# STM_IC.net
KiCad netlist of a schematic drawn in Altium Designer
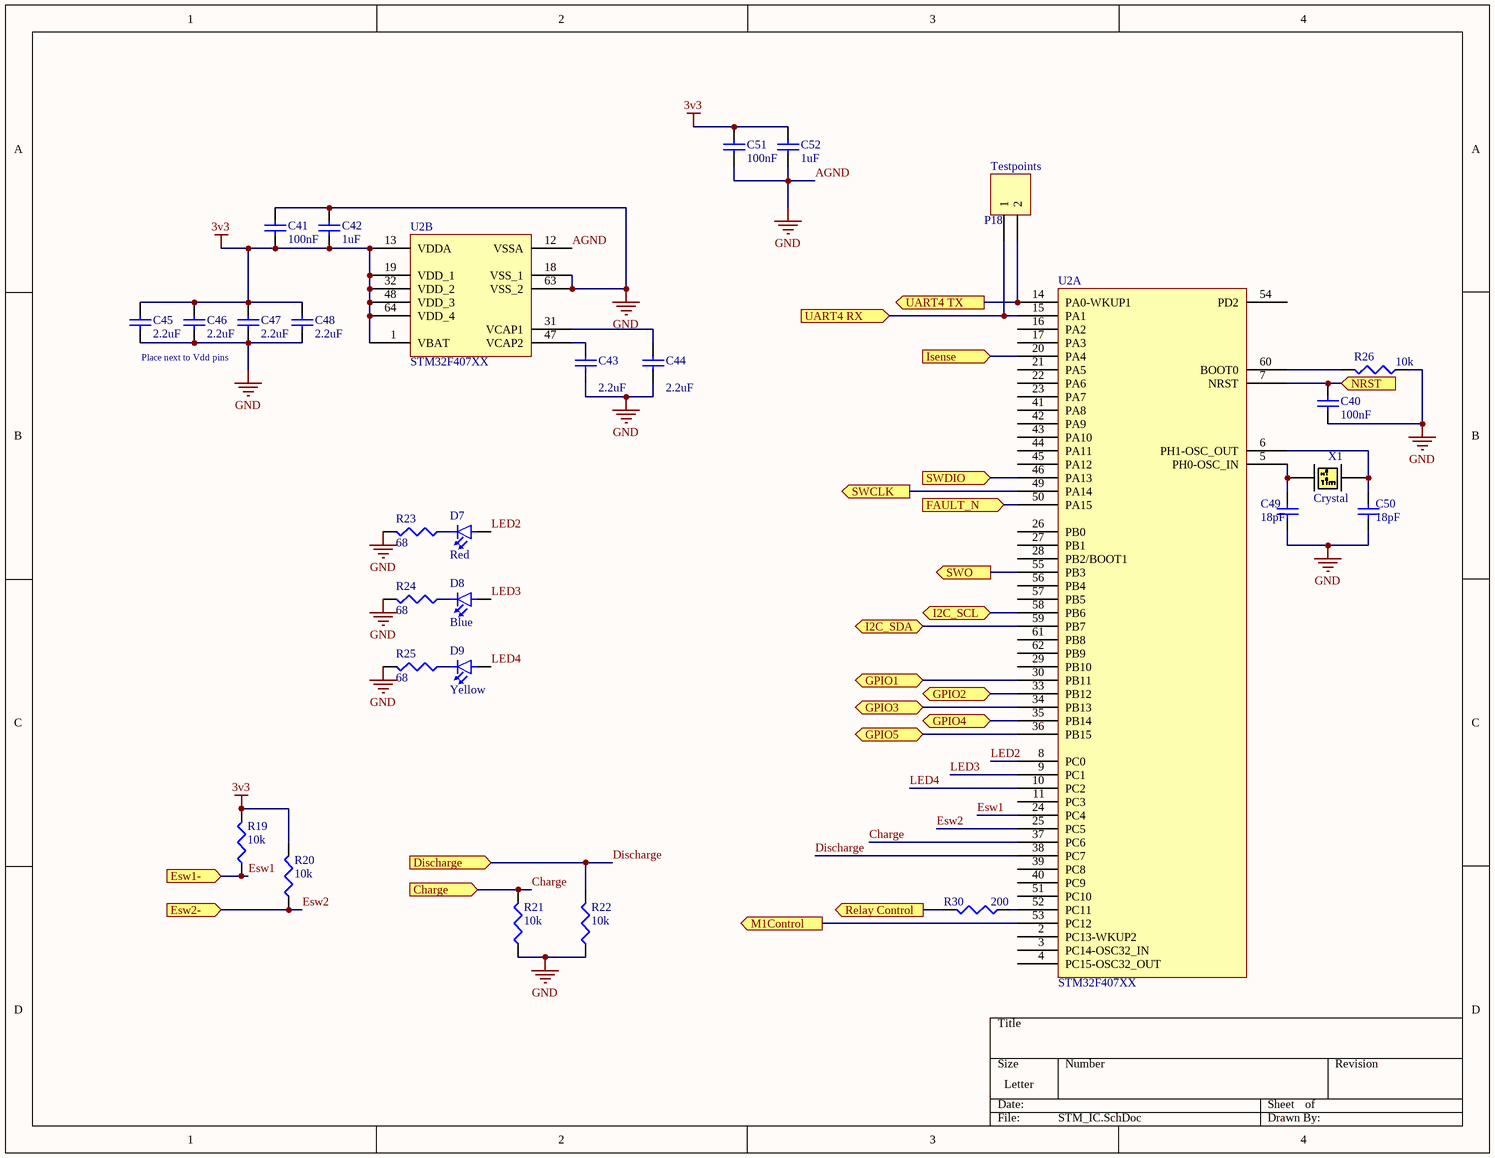
[diagram p0: STM_IC.SchDoc]

(export (version "E")
  (design (tool "Eeschema 10.0.6"))
  (components
    (comp (ref "C40")
      (value "100nF")
      (footprint "SMD0603")
      (description "Ceramic Chip Capacitor")
      (fields (field (name "Comment") "Cap"))
      (libsource (lib "Components") (part "Capacitor Ceramic"))
    )
    (comp (ref "C41")
      (value "100nF")
      (footprint "SMD0603")
      (description "Ceramic Chip Capacitor")
      (fields (field (name "Comment") "Cap"))
      (libsource (lib "Components") (part "Capacitor Ceramic"))
    )
    (comp (ref "C42")
      (value "1uF")
      (footprint "SMD0603")
      (description "Ceramic Chip Capacitor")
      (fields (field (name "Comment") "Cap"))
      (libsource (lib "Components") (part "Capacitor Ceramic"))
    )
    (comp (ref "C43")
      (value "2.2uF")
      (footprint "SMD0603")
      (description "Ceramic Chip Capacitor")
      (fields (field (name "Comment") "Cap"))
      (libsource (lib "Components") (part "Capacitor Ceramic"))
    )
    (comp (ref "C44")
      (value "2.2uF")
      (footprint "SMD0603")
      (description "Ceramic Chip Capacitor")
      (fields (field (name "Comment") "Cap"))
      (libsource (lib "Components") (part "Capacitor Ceramic"))
    )
    (comp (ref "C45")
      (value "2.2uF")
      (footprint "SMD0603")
      (description "Ceramic Chip Capacitor")
      (fields (field (name "Comment") "Cap"))
      (libsource (lib "Components") (part "Capacitor Ceramic"))
    )
    (comp (ref "C46")
      (value "2.2uF")
      (footprint "SMD0603")
      (description "Ceramic Chip Capacitor")
      (fields (field (name "Comment") "Cap"))
      (libsource (lib "Components") (part "Capacitor Ceramic"))
    )
    (comp (ref "C47")
      (value "2.2uF")
      (footprint "SMD0603")
      (description "Ceramic Chip Capacitor")
      (fields (field (name "Comment") "Cap"))
      (libsource (lib "Components") (part "Capacitor Ceramic"))
    )
    (comp (ref "C48")
      (value "2.2uF")
      (footprint "SMD0603")
      (description "Ceramic Chip Capacitor")
      (fields (field (name "Comment") "Cap"))
      (libsource (lib "Components") (part "Capacitor Ceramic"))
    )
    (comp (ref "C49")
      (value "18pF")
      (footprint "SMD0603")
      (description "Ceramic Chip Capacitor")
      (fields (field (name "Comment") "Cap"))
      (libsource (lib "Components") (part "Capacitor Ceramic"))
    )
    (comp (ref "C50")
      (value "18pF")
      (footprint "SMD0603")
      (description "Ceramic Chip Capacitor")
      (fields (field (name "Comment") "Cap"))
      (libsource (lib "Components") (part "Capacitor Ceramic"))
    )
    (comp (ref "C51")
      (value "100nF")
      (footprint "SMD0603")
      (description "Ceramic Chip Capacitor")
      (fields (field (name "Comment") "Cap"))
      (libsource (lib "Components") (part "Capacitor Ceramic"))
    )
    (comp (ref "C52")
      (value "1uF")
      (footprint "SMD0603")
      (description "Ceramic Chip Capacitor")
      (fields (field (name "Comment") "Cap"))
      (libsource (lib "Components") (part "Capacitor Ceramic"))
    )
    (comp (ref "D7")
      (value "LED")
      (footprint "SMD0805_LED")
      (fields (field (name "COLOR") "Red"))
      (libsource (lib "Components") (part "LED"))
    )
    (comp (ref "D8")
      (value "LED")
      (footprint "SMD0805_LED")
      (fields (field (name "COLOR") "Blue"))
      (libsource (lib "Components") (part "LED"))
    )
    (comp (ref "D9")
      (value "LED")
      (footprint "SMD0805_LED")
      (fields (field (name "COLOR") "Yellow"))
      (libsource (lib "Components") (part "LED"))
    )
    (comp (ref "P18")
      (value "Testpoints")
      (footprint "Header 2x1")
      (description "Header, 2-Pin")
      (libsource (lib "Components") (part "Header 2x1"))
    )
    (comp (ref "R19")
      (value "10k")
      (footprint "SMD0603")
      (description "Resistor")
      (fields (field (name "Comment") "Res"))
      (libsource (lib "Components") (part "Resistor"))
    )
    (comp (ref "R20")
      (value "10k")
      (footprint "SMD0603")
      (description "Resistor")
      (fields (field (name "Comment") "Res"))
      (libsource (lib "Components") (part "Resistor"))
    )
    (comp (ref "R21")
      (value "10k")
      (footprint "SMD0603")
      (description "Resistor")
      (fields (field (name "Comment") "Res"))
      (libsource (lib "Components") (part "Resistor"))
    )
    (comp (ref "R22")
      (value "10k")
      (footprint "SMD0603")
      (description "Resistor")
      (fields (field (name "Comment") "Res"))
      (libsource (lib "Components") (part "Resistor"))
    )
    (comp (ref "R23")
      (value "68")
      (footprint "SMD0603")
      (description "Resistor")
      (fields (field (name "Comment") "Res"))
      (libsource (lib "Components") (part "Resistor"))
    )
    (comp (ref "R24")
      (value "68")
      (footprint "SMD0603")
      (description "Resistor")
      (fields (field (name "Comment") "Res"))
      (libsource (lib "Components") (part "Resistor"))
    )
    (comp (ref "R25")
      (value "68")
      (footprint "SMD0603")
      (description "Resistor")
      (fields (field (name "Comment") "Res"))
      (libsource (lib "Components") (part "Resistor"))
    )
    (comp (ref "R26")
      (value "10k")
      (footprint "SMD0603")
      (description "Resistor")
      (fields (field (name "Comment") "Res"))
      (libsource (lib "Components") (part "Resistor"))
    )
    (comp (ref "R30")
      (value "200")
      (footprint "SMD0603")
      (description "Resistor")
      (fields (field (name "Comment") "Res"))
      (libsource (lib "Components") (part "Resistor"))
    )
    (comp (ref "U2")
      (value "STM32F407XX")
      (footprint "LQFP64")
      (libsource (lib "Components") (part "STM32F407_LQFP64"))
    )
    (comp (ref "X1") (value "Crystal") (footprint "ABMM2-OSC") (libsource (lib "Schlib1") (part "Crystal")))
  )
  (nets
    (net (code "1") (name "/Charge") (class "Default")
      (node (ref "R21") (pin "2") (pinfunction "2_2") (pintype "passive"))
      (node (ref "U2") (pin "37") (pinfunction "PC6_37") (pintype "passive"))
    )
    (net (code "2") (name "/Discharge") (class "Default")
      (node (ref "R22") (pin "2") (pinfunction "2_2") (pintype "passive"))
      (node (ref "U2") (pin "38") (pinfunction "PC7_38") (pintype "passive"))
    )
    (net (code "3") (name "/Esw1") (class "Default")
      (node (ref "R19") (pin "1") (pinfunction "1_1") (pintype "passive"))
      (node (ref "U2") (pin "24") (pinfunction "PC4_24") (pintype "passive"))
    )
    (net (code "4") (name "/Esw2") (class "Default")
      (node (ref "R20") (pin "1") (pinfunction "1_1") (pintype "passive"))
      (node (ref "U2") (pin "25") (pinfunction "PC5_25") (pintype "passive"))
    )
    (net (code "5") (name "/FAULT_N") (class "Default")
      (node (ref "U2") (pin "50") (pinfunction "PA15_50") (pintype "passive"))
    )
    (net (code "6") (name "/GPIO1") (class "Default")
      (node (ref "U2") (pin "30") (pinfunction "PB11_30") (pintype "passive"))
    )
    (net (code "7") (name "/GPIO2") (class "Default")
      (node (ref "U2") (pin "33") (pinfunction "PB12_33") (pintype "passive"))
    )
    (net (code "8") (name "/GPIO3") (class "Default")
      (node (ref "U2") (pin "34") (pinfunction "PB13_34") (pintype "passive"))
    )
    (net (code "9") (name "/GPIO4") (class "Default")
      (node (ref "U2") (pin "35") (pinfunction "PB14_35") (pintype "passive"))
    )
    (net (code "10") (name "/GPIO5") (class "Default")
      (node (ref "U2") (pin "36") (pinfunction "PB15_36") (pintype "passive"))
    )
    (net (code "11") (name "/I2C_SCL") (class "Default")
      (node (ref "U2") (pin "58") (pinfunction "PB6_58") (pintype "passive"))
    )
    (net (code "12") (name "/I2C_SDA") (class "Default")
      (node (ref "U2") (pin "59") (pinfunction "PB7_59") (pintype "passive"))
    )
    (net (code "13") (name "/Isense") (class "Default")
      (node (ref "U2") (pin "20") (pinfunction "PA4_20") (pintype "passive"))
    )
    (net (code "14") (name "/LED2") (class "Default")
      (node (ref "D7") (pin "1") (pinfunction "Anode_(+)_1") (pintype "passive"))
      (node (ref "U2") (pin "8") (pinfunction "PC0_8") (pintype "passive"))
    )
    (net (code "15") (name "/LED3") (class "Default")
      (node (ref "D8") (pin "1") (pinfunction "Anode_(+)_1") (pintype "passive"))
      (node (ref "U2") (pin "9") (pinfunction "PC1_9") (pintype "passive"))
    )
    (net (code "16") (name "/LED4") (class "Default")
      (node (ref "D9") (pin "1") (pinfunction "Anode_(+)_1") (pintype "passive"))
      (node (ref "U2") (pin "10") (pinfunction "PC2_10") (pintype "passive"))
    )
    (net (code "17") (name "/M1Control") (class "Default")
      (node (ref "U2") (pin "53") (pinfunction "PC12_53") (pintype "passive"))
    )
    (net (code "18") (name "/NRST") (class "Default")
      (node (ref "C40") (pin "2") (pinfunction "2_2") (pintype "passive"))
      (node (ref "U2") (pin "7") (pinfunction "NRST_7") (pintype "passive"))
    )
    (net (code "19") (name "/Relay Control") (class "Default")
      (node (ref "R30") (pin "2") (pinfunction "2_2") (pintype "passive"))
    )
    (net (code "20") (name "/SWCLK") (class "Default")
      (node (ref "U2") (pin "49") (pinfunction "PA14_49") (pintype "passive"))
    )
    (net (code "21") (name "/SWDIO") (class "Default")
      (node (ref "U2") (pin "46") (pinfunction "PA13_46") (pintype "passive"))
    )
    (net (code "22") (name "/SWO") (class "Default")
      (node (ref "U2") (pin "55") (pinfunction "PB3_55") (pintype "passive"))
    )
    (net (code "23") (name "/UART4 RX") (class "Default")
      (node (ref "P18") (pin "1") (pinfunction "1_1") (pintype "passive"))
      (node (ref "U2") (pin "15") (pinfunction "PA1_15") (pintype "passive"))
    )
    (net (code "24") (name "/UART4 TX") (class "Default")
      (node (ref "P18") (pin "2") (pinfunction "2_2") (pintype "passive"))
      (node (ref "U2") (pin "14") (pinfunction "PA0-WKUP1_14") (pintype "passive"))
    )
    (net (code "25") (name "3v3") (class "Default")
      (node (ref "C41") (pin "1") (pinfunction "1_1") (pintype "passive"))
      (node (ref "C42") (pin "1") (pinfunction "1_1") (pintype "passive"))
      (node (ref "C45") (pin "2") (pinfunction "2_2") (pintype "passive"))
      (node (ref "C46") (pin "2") (pinfunction "2_2") (pintype "passive"))
      (node (ref "C47") (pin "2") (pinfunction "2_2") (pintype "passive"))
      (node (ref "C48") (pin "2") (pinfunction "2_2") (pintype "passive"))
      (node (ref "C51") (pin "2") (pinfunction "2_2") (pintype "passive"))
      (node (ref "C52") (pin "2") (pinfunction "2_2") (pintype "passive"))
      (node (ref "R19") (pin "2") (pinfunction "2_2") (pintype "passive"))
      (node (ref "R20") (pin "2") (pinfunction "2_2") (pintype "passive"))
      (node (ref "U2") (pin "1") (pinfunction "VBAT_1") (pintype "passive"))
      (node (ref "U2") (pin "13") (pinfunction "VDDA_13") (pintype "passive"))
      (node (ref "U2") (pin "19") (pinfunction "VDD_1_19") (pintype "passive"))
      (node (ref "U2") (pin "32") (pinfunction "VDD_2_32") (pintype "passive"))
      (node (ref "U2") (pin "48") (pinfunction "VDD_3_48") (pintype "passive"))
      (node (ref "U2") (pin "64") (pinfunction "VDD_4_64") (pintype "passive"))
    )
    (net (code "26") (name "GND") (class "Default")
      (node (ref "C40") (pin "1") (pinfunction "1_1") (pintype "passive"))
      (node (ref "C41") (pin "2") (pinfunction "2_2") (pintype "passive"))
      (node (ref "C42") (pin "2") (pinfunction "2_2") (pintype "passive"))
      (node (ref "C43") (pin "1") (pinfunction "1_1") (pintype "passive"))
      (node (ref "C44") (pin "1") (pinfunction "1_1") (pintype "passive"))
      (node (ref "C45") (pin "1") (pinfunction "1_1") (pintype "passive"))
      (node (ref "C46") (pin "1") (pinfunction "1_1") (pintype "passive"))
      (node (ref "C47") (pin "1") (pinfunction "1_1") (pintype "passive"))
      (node (ref "C48") (pin "1") (pinfunction "1_1") (pintype "passive"))
      (node (ref "C49") (pin "1") (pinfunction "1_1") (pintype "passive"))
      (node (ref "C50") (pin "1") (pinfunction "1_1") (pintype "passive"))
      (node (ref "C51") (pin "1") (pinfunction "1_1") (pintype "passive"))
      (node (ref "C52") (pin "1") (pinfunction "1_1") (pintype "passive"))
      (node (ref "R21") (pin "1") (pinfunction "1_1") (pintype "passive"))
      (node (ref "R22") (pin "1") (pinfunction "1_1") (pintype "passive"))
      (node (ref "R23") (pin "2") (pinfunction "2_2") (pintype "passive"))
      (node (ref "R24") (pin "2") (pinfunction "2_2") (pintype "passive"))
      (node (ref "R25") (pin "2") (pinfunction "2_2") (pintype "passive"))
      (node (ref "R26") (pin "1") (pinfunction "1_1") (pintype "passive"))
      (node (ref "U2") (pin "12") (pinfunction "VSSA_12") (pintype "passive"))
      (node (ref "U2") (pin "18") (pinfunction "VSS_1_18") (pintype "passive"))
      (node (ref "U2") (pin "63") (pinfunction "VSS_2_63") (pintype "passive"))
    )
    (net (code "27") (name "Net-(D7-Cathode_(-))") (class "Default")
      (node (ref "D7") (pin "2") (pinfunction "Cathode_(-)_2") (pintype "passive"))
      (node (ref "R23") (pin "1") (pinfunction "1_1") (pintype "passive"))
    )
    (net (code "28") (name "Net-(D8-Cathode_(-))") (class "Default")
      (node (ref "D8") (pin "2") (pinfunction "Cathode_(-)_2") (pintype "passive"))
      (node (ref "R24") (pin "1") (pinfunction "1_1") (pintype "passive"))
    )
    (net (code "29") (name "Net-(D9-Cathode_(-))") (class "Default")
      (node (ref "D9") (pin "2") (pinfunction "Cathode_(-)_2") (pintype "passive"))
      (node (ref "R25") (pin "1") (pinfunction "1_1") (pintype "passive"))
    )
    (net (code "30") (name "Net-(U2A-BOOT0)") (class "Default")
      (node (ref "R26") (pin "2") (pinfunction "2_2") (pintype "passive"))
      (node (ref "U2") (pin "60") (pinfunction "BOOT0_60") (pintype "passive"))
    )
    (net (code "31") (name "Net-(U2A-PC11)") (class "Default")
      (node (ref "R30") (pin "1") (pinfunction "1_1") (pintype "passive"))
      (node (ref "U2") (pin "52") (pinfunction "PC11_52") (pintype "passive"))
    )
    (net (code "32") (name "Net-(U2A-PH0-OSC_IN)") (class "Default")
      (node (ref "C49") (pin "2") (pinfunction "2_2") (pintype "passive"))
      (node (ref "U2") (pin "5") (pinfunction "PH0-OSC_IN_5") (pintype "passive"))
      (node (ref "X1") (pin "1") (pintype "passive"))
    )
    (net (code "33") (name "Net-(U2A-PH1-OSC_OUT)") (class "Default")
      (node (ref "C50") (pin "2") (pinfunction "2_2") (pintype "passive"))
      (node (ref "U2") (pin "6") (pinfunction "PH1-OSC_OUT_6") (pintype "passive"))
      (node (ref "X1") (pin "2") (pintype "passive"))
    )
    (net (code "34") (name "Net-(U2B-VCAP1)") (class "Default")
      (node (ref "C44") (pin "2") (pinfunction "2_2") (pintype "passive"))
      (node (ref "U2") (pin "31") (pinfunction "VCAP1_31") (pintype "passive"))
    )
    (net (code "35") (name "Net-(U2B-VCAP2)") (class "Default")
      (node (ref "C43") (pin "2") (pinfunction "2_2") (pintype "passive"))
      (node (ref "U2") (pin "47") (pinfunction "VCAP2_47") (pintype "passive"))
    )
    (net (code "36") (name "unconnected-(U2A-PA2-Pad16)") (class "Default")
      (node (ref "U2") (pin "16") (pinfunction "PA2_16") (pintype "passive"))
    )
    (net (code "37") (name "unconnected-(U2A-PA3-Pad17)") (class "Default")
      (node (ref "U2") (pin "17") (pinfunction "PA3_17") (pintype "passive"))
    )
    (net (code "38") (name "unconnected-(U2A-PA5-Pad21)") (class "Default")
      (node (ref "U2") (pin "21") (pinfunction "PA5_21") (pintype "passive"))
    )
    (net (code "39") (name "unconnected-(U2A-PA6-Pad22)") (class "Default")
      (node (ref "U2") (pin "22") (pinfunction "PA6_22") (pintype "passive"))
    )
    (net (code "40") (name "unconnected-(U2A-PA7-Pad23)") (class "Default")
      (node (ref "U2") (pin "23") (pinfunction "PA7_23") (pintype "passive"))
    )
    (net (code "41") (name "unconnected-(U2A-PA8-Pad41)") (class "Default")
      (node (ref "U2") (pin "41") (pinfunction "PA8_41") (pintype "passive"))
    )
    (net (code "42") (name "unconnected-(U2A-PA9-Pad42)") (class "Default")
      (node (ref "U2") (pin "42") (pinfunction "PA9_42") (pintype "passive"))
    )
    (net (code "43") (name "unconnected-(U2A-PA10-Pad43)") (class "Default")
      (node (ref "U2") (pin "43") (pinfunction "PA10_43") (pintype "passive"))
    )
    (net (code "44") (name "unconnected-(U2A-PA11-Pad44)") (class "Default")
      (node (ref "U2") (pin "44") (pinfunction "PA11_44") (pintype "passive"))
    )
    (net (code "45") (name "unconnected-(U2A-PA12-Pad45)") (class "Default")
      (node (ref "U2") (pin "45") (pinfunction "PA12_45") (pintype "passive"))
    )
    (net (code "46") (name "unconnected-(U2A-PB0-Pad26)") (class "Default")
      (node (ref "U2") (pin "26") (pinfunction "PB0_26") (pintype "passive"))
    )
    (net (code "47") (name "unconnected-(U2A-PB1-Pad27)") (class "Default")
      (node (ref "U2") (pin "27") (pinfunction "PB1_27") (pintype "passive"))
    )
    (net (code "48") (name "unconnected-(U2A-PB2{slash}BOOT1-Pad28)") (class "Default")
      (node (ref "U2") (pin "28") (pinfunction "PB2/BOOT1_28") (pintype "passive"))
    )
    (net (code "49") (name "unconnected-(U2A-PB4-Pad56)") (class "Default")
      (node (ref "U2") (pin "56") (pinfunction "PB4_56") (pintype "passive"))
    )
    (net (code "50") (name "unconnected-(U2A-PB5-Pad57)") (class "Default")
      (node (ref "U2") (pin "57") (pinfunction "PB5_57") (pintype "passive"))
    )
    (net (code "51") (name "unconnected-(U2A-PB8-Pad61)") (class "Default")
      (node (ref "U2") (pin "61") (pinfunction "PB8_61") (pintype "passive"))
    )
    (net (code "52") (name "unconnected-(U2A-PB9-Pad62)") (class "Default")
      (node (ref "U2") (pin "62") (pinfunction "PB9_62") (pintype "passive"))
    )
    (net (code "53") (name "unconnected-(U2A-PB10-Pad29)") (class "Default")
      (node (ref "U2") (pin "29") (pinfunction "PB10_29") (pintype "passive"))
    )
    (net (code "54") (name "unconnected-(U2A-PC3-Pad11)") (class "Default")
      (node (ref "U2") (pin "11") (pinfunction "PC3_11") (pintype "passive"))
    )
    (net (code "55") (name "unconnected-(U2A-PC8-Pad39)") (class "Default")
      (node (ref "U2") (pin "39") (pinfunction "PC8_39") (pintype "passive"))
    )
    (net (code "56") (name "unconnected-(U2A-PC9-Pad40)") (class "Default")
      (node (ref "U2") (pin "40") (pinfunction "PC9_40") (pintype "passive"))
    )
    (net (code "57") (name "unconnected-(U2A-PC10-Pad51)") (class "Default")
      (node (ref "U2") (pin "51") (pinfunction "PC10_51") (pintype "passive"))
    )
    (net (code "58") (name "unconnected-(U2A-PC13-WKUP2-Pad2)") (class "Default")
      (node (ref "U2") (pin "2") (pinfunction "PC13-WKUP2_2") (pintype "passive"))
    )
    (net (code "59") (name "unconnected-(U2A-PC14-OSC32_IN-Pad3)") (class "Default")
      (node (ref "U2") (pin "3") (pinfunction "PC14-OSC32_IN_3") (pintype "passive"))
    )
    (net (code "60") (name "unconnected-(U2A-PC15-OSC32_OUT-Pad4)") (class "Default")
      (node (ref "U2") (pin "4") (pinfunction "PC15-OSC32_OUT_4") (pintype "passive"))
    )
    (net (code "61") (name "unconnected-(U2A-PD2-Pad54)") (class "Default")
      (node (ref "U2") (pin "54") (pinfunction "PD2_54") (pintype "passive"))
    )
  )
)
